# CLassD_amp_v1.net
KiCad netlist of a schematic drawn in Altium Designer
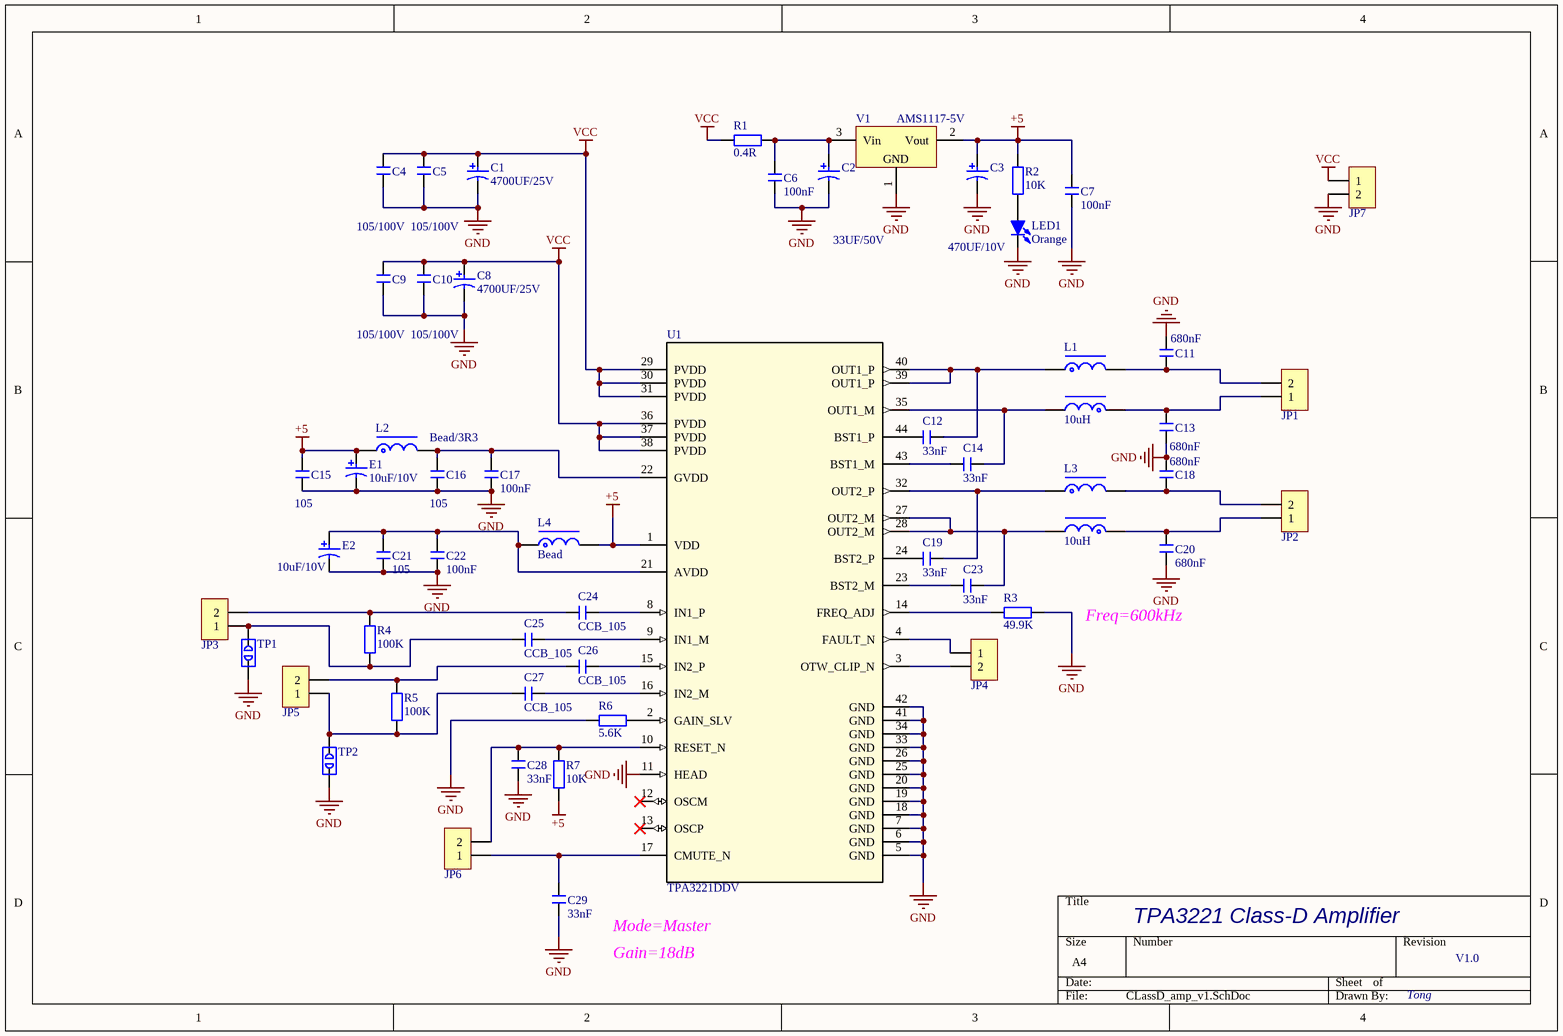
[diagram p0: CLassD_amp_v1.SchDoc]

(export (version "E")
  (design (tool "Eeschema 10.0.6"))
  (components
    (comp (ref "C1")
      (value "4700UF/25V")
      (footprint "CAP 7.5*16*31.5")
      (description "铝电解电容-直插")
      (libsource (lib "A") (part "Cap-AE-RAD"))
    )
    (comp (ref "C2")
      (value "33UF/50V")
      (footprint "CAP 2.5*6.3*11.2")
      (description "铝电解电容-直插")
      (libsource (lib "A") (part "Cap-AE-RAD"))
    )
    (comp (ref "C3")
      (value "470UF/10V")
      (footprint "CAP 2.5*6.3*11.2")
      (description "铝电解电容-直插")
      (libsource (lib "A") (part "Cap-AE-RAD"))
    )
    (comp (ref "C4")
      (value "105/100V")
      (footprint "C 1206_little")
      (description "瓷片电容-贴片")
      (libsource (lib "A") (part "Cap-CER-SMD"))
    )
    (comp (ref "C5")
      (value "105/100V")
      (footprint "C 1206_little")
      (description "瓷片电容-贴片")
      (libsource (lib "A") (part "Cap-CER-SMD"))
    )
    (comp (ref "C6")
      (value "100nF")
      (footprint "C 0603")
      (description "瓷片电容-贴片")
      (libsource (lib "A") (part "Cap-CER-SMD"))
    )
    (comp (ref "C7")
      (value "100nF")
      (footprint "C 0603")
      (description "瓷片电容-贴片")
      (libsource (lib "A") (part "Cap-CER-SMD"))
    )
    (comp (ref "C8")
      (value "4700UF/25V")
      (footprint "CAP 7.5*16*31.5")
      (description "铝电解电容-直插")
      (libsource (lib "A") (part "Cap-AE-RAD"))
    )
    (comp (ref "C9")
      (value "105/100V")
      (footprint "C 1206_little")
      (description "瓷片电容-贴片")
      (libsource (lib "A") (part "Cap-CER-SMD"))
    )
    (comp (ref "C10")
      (value "105/100V")
      (footprint "C 1206_little")
      (description "瓷片电容-贴片")
      (libsource (lib "A") (part "Cap-CER-SMD"))
    )
    (comp (ref "C11")
      (value "680nF")
      (footprint "Xcap2")
      (description "瓷片电容-贴片")
      (libsource (lib "A") (part "Cap-CER-SMD"))
    )
    (comp (ref "C12")
      (value "33nF")
      (footprint "C 0603")
      (description "瓷片电容-贴片")
      (libsource (lib "A") (part "Cap-CER-SMD"))
    )
    (comp (ref "C13")
      (value "680nF")
      (footprint "Xcap2")
      (description "瓷片电容-贴片")
      (libsource (lib "A") (part "Cap-CER-SMD"))
    )
    (comp (ref "C14")
      (value "33nF")
      (footprint "C 0603")
      (description "瓷片电容-贴片")
      (libsource (lib "A") (part "Cap-CER-SMD"))
    )
    (comp (ref "C15")
      (value "105")
      (footprint "C 0603")
      (description "瓷片电容-贴片")
      (libsource (lib "A") (part "Cap-CER-SMD"))
    )
    (comp (ref "C16")
      (value "105")
      (footprint "C 0603")
      (description "瓷片电容-贴片")
      (libsource (lib "A") (part "Cap-CER-SMD"))
    )
    (comp (ref "C17")
      (value "100nF")
      (footprint "C 0603")
      (description "瓷片电容-贴片")
      (libsource (lib "A") (part "Cap-CER-SMD"))
    )
    (comp (ref "C18")
      (value "680nF")
      (footprint "Xcap2")
      (description "瓷片电容-贴片")
      (libsource (lib "A") (part "Cap-CER-SMD"))
    )
    (comp (ref "C19")
      (value "33nF")
      (footprint "C 0603")
      (description "瓷片电容-贴片")
      (libsource (lib "A") (part "Cap-CER-SMD"))
    )
    (comp (ref "C20")
      (value "680nF")
      (footprint "Xcap2")
      (description "瓷片电容-贴片")
      (libsource (lib "A") (part "Cap-CER-SMD"))
    )
    (comp (ref "C21")
      (value "105")
      (footprint "C 0603")
      (description "瓷片电容-贴片")
      (libsource (lib "A") (part "Cap-CER-SMD"))
    )
    (comp (ref "C22")
      (value "100nF")
      (footprint "C 0603")
      (description "瓷片电容-贴片")
      (libsource (lib "A") (part "Cap-CER-SMD"))
    )
    (comp (ref "C23")
      (value "33nF")
      (footprint "C 0603")
      (description "瓷片电容-贴片")
      (libsource (lib "A") (part "Cap-CER-SMD"))
    )
    (comp (ref "C24")
      (value "CCB_105")
      (footprint "CCB_Cap_7.5mm")
      (description "瓷片电容-贴片")
      (libsource (lib "A") (part "Cap-CER-SMD"))
    )
    (comp (ref "C25")
      (value "CCB_105")
      (footprint "CCB_Cap_7.5mm")
      (description "瓷片电容-贴片")
      (libsource (lib "A") (part "Cap-CER-SMD"))
    )
    (comp (ref "C26")
      (value "CCB_105")
      (footprint "CCB_Cap_7.5mm")
      (description "瓷片电容-贴片")
      (libsource (lib "A") (part "Cap-CER-SMD"))
    )
    (comp (ref "C27")
      (value "CCB_105")
      (footprint "CCB_Cap_7.5mm")
      (description "瓷片电容-贴片")
      (libsource (lib "A") (part "Cap-CER-SMD"))
    )
    (comp (ref "C28")
      (value "33nF")
      (footprint "C 0603")
      (description "瓷片电容-贴片")
      (libsource (lib "A") (part "Cap-CER-SMD"))
    )
    (comp (ref "C29")
      (value "33nF")
      (footprint "C 0603")
      (description "瓷片电容-贴片")
      (libsource (lib "A") (part "Cap-CER-SMD"))
    )
    (comp (ref "E1")
      (value "10uF/10V")
      (footprint "CD B(3528)")
      (description "钽电解电容-贴片")
      (libsource (lib "A") (part "Cap-TAN-SMD"))
    )
    (comp (ref "E2")
      (value "10uF/10V")
      (footprint "CD B(3528)")
      (description "钽电解电容-贴片")
      (libsource (lib "A") (part "Cap-TAN-SMD"))
    )
    (comp (ref "JP1")
      (value "HDR-1X2")
      (footprint "KF128-3.81-2P")
      (description "2P接插件")
      (fields (field (name "版权归属") "源创客"))
      (libsource (lib "A") (part "Header 2"))
    )
    (comp (ref "JP2")
      (value "HDR-1X2")
      (footprint "KF128-3.81-2P")
      (description "2P接插件")
      (fields (field (name "版权归属") "源创客"))
      (libsource (lib "A") (part "Header 2"))
    )
    (comp (ref "JP3")
      (value "HDR-1X2")
      (footprint "HDR-1X2")
      (description "2P接插件")
      (fields (field (name "版权归属") "源创客"))
      (libsource (lib "") (part "Header 2_2"))
    )
    (comp (ref "JP4")
      (value "HDR-1X2")
      (footprint "HDR-1X2")
      (description "2P接插件")
      (fields (field (name "版权归属") "源创客"))
      (libsource (lib "") (part "Header 2_1"))
    )
    (comp (ref "JP5")
      (value "HDR-1X2")
      (footprint "HDR-1X2")
      (description "2P接插件")
      (fields (field (name "版权归属") "源创客"))
      (libsource (lib "") (part "Header 2_2"))
    )
    (comp (ref "JP6")
      (value "HDR-1X2")
      (footprint "HDR-1X2")
      (description "2P接插件")
      (fields (field (name "版权归属") "源创客"))
      (libsource (lib "") (part "Header 2_2"))
    )
    (comp (ref "JP7")
      (value "HDR-1X2")
      (footprint "KF128-3.81-2P")
      (description "2P接插件")
      (fields (field (name "版权归属") "源创客"))
      (libsource (lib "") (part "Header 2_1"))
    )
    (comp (ref "L1") (value "10uH") (footprint "L") (libsource (lib "A") (part "L")))
    (comp (ref "L2")
      (value "Bead/3R3")
      (footprint "L 0805")
      (description "贴片电感-小功率")
      (libsource (lib "A") (part "Ind-Beads-SMD"))
    )
    (comp (ref "L3") (value "10uH") (footprint "L") (libsource (lib "A") (part "L")))
    (comp (ref "L4")
      (value "Bead")
      (footprint "L 0805")
      (description "贴片电感-小功率")
      (libsource (lib "A") (part "Ind-Beads-SMD"))
    )
    (comp (ref "LED1")
      (value "Orange")
      (footprint "LED 0603R")
      (description "LED")
      (fields (field (name "版权归属") "源创客"))
      (libsource (lib "A") (part "LED-SMD"))
    )
    (comp (ref "R1")
      (value "0.4R")
      (footprint "Res-SMD-1206")
      (description "固定电阻器-贴片")
      (libsource (lib "A") (part "Res-Fixed-SMD"))
    )
    (comp (ref "R2")
      (value "10K")
      (footprint "Res-SMD-0603")
      (description "固定电阻器-贴片")
      (libsource (lib "A") (part "Res-Fixed-SMD"))
    )
    (comp (ref "R3")
      (value "49.9K")
      (footprint "Res-SMD-0603")
      (description "固定电阻器-贴片")
      (libsource (lib "A") (part "Res-Fixed-SMD"))
    )
    (comp (ref "R4")
      (value "100K")
      (footprint "Res-SMD-0603")
      (description "固定电阻器-贴片")
      (libsource (lib "A") (part "Res-Fixed-SMD"))
    )
    (comp (ref "R5")
      (value "100K")
      (footprint "Res-SMD-0603")
      (description "固定电阻器-贴片")
      (libsource (lib "A") (part "Res-Fixed-SMD"))
    )
    (comp (ref "R6")
      (value "5.6K")
      (footprint "Res-SMD-0603")
      (description "固定电阻器-贴片")
      (libsource (lib "A") (part "Res-Fixed-SMD"))
    )
    (comp (ref "R7")
      (value "10K")
      (footprint "Res-SMD-0603")
      (description "固定电阻器-贴片")
      (libsource (lib "A") (part "Res-Fixed-SMD"))
    )
    (comp (ref "TP1")
      (value "~")
      (footprint "DEBUG PAD2")
      (description "调试断点焊盘")
      (fields (field (name "版权归属") "源创客"))
      (libsource (lib "A") (part "DEBUG"))
    )
    (comp (ref "TP2")
      (value "~")
      (footprint "DEBUG PAD2")
      (description "调试断点焊盘")
      (fields (field (name "版权归属") "源创客"))
      (libsource (lib "A") (part "DEBUG"))
    )
    (comp (ref "U1")
      (value "TPA3221DDV")
      (footprint "DDV0044D_N")
      (description "No Description Available")
      (fields
        (field (name "MANUFACTURER") "Texas Instruments")
        (field (name "PARTNUMBER") "TPA3221DDVR")
        (field (name "COPYRIGHT") "Copyright (C) 2018 Accelerated Designs. All rights reserved")
      )
      (libsource (lib "A") (part "TPA3221DDV"))
    )
    (comp (ref "V1")
      (value "AMS1117-5V")
      (footprint "SOT223_L")
      (description "三端稳压芯片")
      (fields (field (name "版权归属") "源创客"))
      (libsource (lib "A") (part "AMS1117"))
    )
  )
  (nets
    (net (code "1") (name "+5") (class "Default")
      (node (ref "C15") (pin "2") (pinfunction "2_2") (pintype "passive"))
      (node (ref "C3") (pin "A") (pinfunction "A_A") (pintype "passive"))
      (node (ref "C7") (pin "2") (pinfunction "2_2") (pintype "passive"))
      (node (ref "E1") (pin "A") (pinfunction "A_A") (pintype "passive"))
      (node (ref "L2") (pin "1") (pinfunction "1_1") (pintype "passive"))
      (node (ref "L4") (pin "2") (pinfunction "2_2") (pintype "passive"))
      (node (ref "R2") (pin "2") (pinfunction "2_2") (pintype "passive"))
      (node (ref "R7") (pin "1") (pinfunction "1_1") (pintype "passive"))
      (node (ref "U1") (pin "1") (pinfunction "VDD_1") (pintype "power_in"))
      (node (ref "V1") (pin "2") (pinfunction "Vout_2") (pintype "passive"))
    )
    (net (code "2") (name "GND") (class "Default")
      (node (ref "C1") (pin "K") (pinfunction "K_K") (pintype "passive"))
      (node (ref "C10") (pin "2") (pinfunction "2_2") (pintype "passive"))
      (node (ref "C11") (pin "2") (pinfunction "2_2") (pintype "passive"))
      (node (ref "C13") (pin "2") (pinfunction "2_2") (pintype "passive"))
      (node (ref "C15") (pin "1") (pinfunction "1_1") (pintype "passive"))
      (node (ref "C16") (pin "1") (pinfunction "1_1") (pintype "passive"))
      (node (ref "C17") (pin "1") (pinfunction "1_1") (pintype "passive"))
      (node (ref "C18") (pin "2") (pinfunction "2_2") (pintype "passive"))
      (node (ref "C2") (pin "K") (pinfunction "K_K") (pintype "passive"))
      (node (ref "C20") (pin "2") (pinfunction "2_2") (pintype "passive"))
      (node (ref "C21") (pin "1") (pinfunction "1_1") (pintype "passive"))
      (node (ref "C22") (pin "1") (pinfunction "1_1") (pintype "passive"))
      (node (ref "C28") (pin "2") (pinfunction "2_2") (pintype "passive"))
      (node (ref "C29") (pin "2") (pinfunction "2_2") (pintype "passive"))
      (node (ref "C3") (pin "K") (pinfunction "K_K") (pintype "passive"))
      (node (ref "C4") (pin "2") (pinfunction "2_2") (pintype "passive"))
      (node (ref "C5") (pin "2") (pinfunction "2_2") (pintype "passive"))
      (node (ref "C6") (pin "1") (pinfunction "1_1") (pintype "passive"))
      (node (ref "C7") (pin "1") (pinfunction "1_1") (pintype "passive"))
      (node (ref "C8") (pin "K") (pinfunction "K_K") (pintype "passive"))
      (node (ref "C9") (pin "2") (pinfunction "2_2") (pintype "passive"))
      (node (ref "E1") (pin "K") (pinfunction "K_K") (pintype "passive"))
      (node (ref "E2") (pin "K") (pinfunction "K_K") (pintype "passive"))
      (node (ref "JP7") (pin "2") (pinfunction "2_2") (pintype "passive"))
      (node (ref "LED1") (pin "2") (pinfunction "K_2") (pintype "passive"))
      (node (ref "R3") (pin "2") (pinfunction "2_2") (pintype "passive"))
      (node (ref "R6") (pin "1") (pinfunction "1_1") (pintype "passive"))
      (node (ref "TP1") (pin "1") (pinfunction "1_1") (pintype "passive"))
      (node (ref "TP2") (pin "1") (pinfunction "1_1") (pintype "passive"))
      (node (ref "U1") (pin "11") (pinfunction "HEAD_11") (pintype "input"))
      (node (ref "U1") (pin "18") (pinfunction "GND_18") (pintype "power_in"))
      (node (ref "U1") (pin "19") (pinfunction "GND_19") (pintype "power_in"))
      (node (ref "U1") (pin "20") (pinfunction "GND_20") (pintype "power_in"))
      (node (ref "U1") (pin "25") (pinfunction "GND_25") (pintype "power_in"))
      (node (ref "U1") (pin "26") (pinfunction "GND_26") (pintype "power_in"))
      (node (ref "U1") (pin "33") (pinfunction "GND_33") (pintype "power_in"))
      (node (ref "U1") (pin "34") (pinfunction "GND_34") (pintype "power_in"))
      (node (ref "U1") (pin "41") (pinfunction "GND_41") (pintype "power_in"))
      (node (ref "U1") (pin "42") (pinfunction "GND_42") (pintype "power_in"))
      (node (ref "U1") (pin "5") (pinfunction "GND_5") (pintype "power_in"))
      (node (ref "U1") (pin "6") (pinfunction "GND_6") (pintype "power_in"))
      (node (ref "U1") (pin "7") (pinfunction "GND_7") (pintype "power_in"))
      (node (ref "V1") (pin "1") (pinfunction "GND_1") (pintype "passive"))
    )
    (net (code "3") (name "Net-(C11-Pad1)") (class "Default")
      (node (ref "C11") (pin "1") (pinfunction "1_1") (pintype "passive"))
      (node (ref "JP1") (pin "2") (pinfunction "2_2") (pintype "passive"))
      (node (ref "L1") (pin "2") (pinfunction "2_2") (pintype "passive"))
    )
    (net (code "4") (name "Net-(C12-Pad2)") (class "Default")
      (node (ref "C12") (pin "2") (pinfunction "2_2") (pintype "passive"))
      (node (ref "L1") (pin "1") (pinfunction "1_1") (pintype "passive"))
      (node (ref "U1") (pin "39") (pinfunction "OUT1_P_39") (pintype "output"))
      (node (ref "U1") (pin "40") (pinfunction "OUT1_P_40") (pintype "output"))
    )
    (net (code "5") (name "Net-(C13-Pad1)") (class "Default")
      (node (ref "C13") (pin "1") (pinfunction "1_1") (pintype "passive"))
      (node (ref "JP1") (pin "1") (pinfunction "1_1") (pintype "passive"))
      (node (ref "L1") (pin "4") (pinfunction "4_4") (pintype "passive"))
    )
    (net (code "6") (name "Net-(C18-Pad1)") (class "Default")
      (node (ref "C18") (pin "1") (pinfunction "1_1") (pintype "passive"))
      (node (ref "JP2") (pin "2") (pinfunction "2_2") (pintype "passive"))
      (node (ref "L3") (pin "2") (pinfunction "2_2") (pintype "passive"))
    )
    (net (code "7") (name "Net-(C20-Pad1)") (class "Default")
      (node (ref "C20") (pin "1") (pinfunction "1_1") (pintype "passive"))
      (node (ref "JP2") (pin "1") (pinfunction "1_1") (pintype "passive"))
      (node (ref "L3") (pin "4") (pinfunction "4_4") (pintype "passive"))
    )
    (net (code "8") (name "Net-(C23-Pad2)") (class "Default")
      (node (ref "C23") (pin "2") (pinfunction "2_2") (pintype "passive"))
      (node (ref "L3") (pin "3") (pinfunction "3_3") (pintype "passive"))
      (node (ref "U1") (pin "27") (pinfunction "OUT2_M_27") (pintype "output"))
      (node (ref "U1") (pin "28") (pinfunction "OUT2_M_28") (pintype "output"))
    )
    (net (code "9") (name "Net-(C24-Pad1)") (class "Default")
      (node (ref "C24") (pin "1") (pinfunction "1_1") (pintype "passive"))
      (node (ref "JP3") (pin "2") (pinfunction "2_2") (pintype "passive"))
      (node (ref "R4") (pin "2") (pinfunction "2_2") (pintype "passive"))
    )
    (net (code "10") (name "Net-(C25-Pad1)") (class "Default")
      (node (ref "C25") (pin "1") (pinfunction "1_1") (pintype "passive"))
      (node (ref "JP3") (pin "1") (pinfunction "1_1") (pintype "passive"))
      (node (ref "R4") (pin "1") (pinfunction "1_1") (pintype "passive"))
      (node (ref "TP1") (pin "2") (pinfunction "2_2") (pintype "passive"))
    )
    (net (code "11") (name "Net-(C26-Pad1)") (class "Default")
      (node (ref "C26") (pin "1") (pinfunction "1_1") (pintype "passive"))
      (node (ref "JP5") (pin "2") (pinfunction "2_2") (pintype "passive"))
      (node (ref "R5") (pin "2") (pinfunction "2_2") (pintype "passive"))
    )
    (net (code "12") (name "Net-(C27-Pad1)") (class "Default")
      (node (ref "C27") (pin "1") (pinfunction "1_1") (pintype "passive"))
      (node (ref "JP5") (pin "1") (pinfunction "1_1") (pintype "passive"))
      (node (ref "R5") (pin "1") (pinfunction "1_1") (pintype "passive"))
      (node (ref "TP2") (pin "2") (pinfunction "2_2") (pintype "passive"))
    )
    (net (code "13") (name "Net-(LED1-A)") (class "Default")
      (node (ref "LED1") (pin "1") (pinfunction "A_1") (pintype "passive"))
      (node (ref "R2") (pin "1") (pinfunction "1_1") (pintype "passive"))
    )
    (net (code "14") (name "Net-(U1-AVDD)") (class "Default")
      (node (ref "C21") (pin "2") (pinfunction "2_2") (pintype "passive"))
      (node (ref "C22") (pin "2") (pinfunction "2_2") (pintype "passive"))
      (node (ref "E2") (pin "A") (pinfunction "A_A") (pintype "passive"))
      (node (ref "L4") (pin "1") (pinfunction "1_1") (pintype "passive"))
      (node (ref "U1") (pin "21") (pinfunction "AVDD_21") (pintype "power_in"))
    )
    (net (code "15") (name "Net-(U1-BST1_M)") (class "Default")
      (node (ref "C14") (pin "1") (pinfunction "1_1") (pintype "passive"))
      (node (ref "U1") (pin "43") (pinfunction "BST1_M_43") (pintype "power_in"))
    )
    (net (code "16") (name "Net-(U1-BST1_P)") (class "Default")
      (node (ref "C12") (pin "1") (pinfunction "1_1") (pintype "passive"))
      (node (ref "U1") (pin "44") (pinfunction "BST1_P_44") (pintype "power_in"))
    )
    (net (code "17") (name "Net-(U1-BST2_M)") (class "Default")
      (node (ref "C23") (pin "1") (pinfunction "1_1") (pintype "passive"))
      (node (ref "U1") (pin "23") (pinfunction "BST2_M_23") (pintype "power_in"))
    )
    (net (code "18") (name "Net-(U1-BST2_P)") (class "Default")
      (node (ref "C19") (pin "1") (pinfunction "1_1") (pintype "passive"))
      (node (ref "U1") (pin "24") (pinfunction "BST2_P_24") (pintype "power_in"))
    )
    (net (code "19") (name "Net-(U1-CMUTE_N)") (class "Default")
      (node (ref "C29") (pin "1") (pinfunction "1_1") (pintype "passive"))
      (node (ref "JP6") (pin "1") (pinfunction "1_1") (pintype "passive"))
      (node (ref "U1") (pin "17") (pinfunction "CMUTE_N_17") (pintype "power_in"))
    )
    (net (code "20") (name "Net-(U1-FAULT_N)") (class "Default")
      (node (ref "JP4") (pin "1") (pinfunction "1_1") (pintype "passive"))
      (node (ref "U1") (pin "4") (pinfunction "FAULT_N_4") (pintype "output"))
    )
    (net (code "21") (name "Net-(U1-FREQ_ADJ)") (class "Default")
      (node (ref "R3") (pin "1") (pinfunction "1_1") (pintype "passive"))
      (node (ref "U1") (pin "14") (pinfunction "FREQ_ADJ_14") (pintype "output"))
    )
    (net (code "22") (name "Net-(U1-GAIN_SLV)") (class "Default")
      (node (ref "R6") (pin "2") (pinfunction "2_2") (pintype "passive"))
      (node (ref "U1") (pin "2") (pinfunction "GAIN_SLV_2") (pintype "input"))
    )
    (net (code "23") (name "Net-(U1-GVDD)") (class "Default")
      (node (ref "C16") (pin "2") (pinfunction "2_2") (pintype "passive"))
      (node (ref "C17") (pin "2") (pinfunction "2_2") (pintype "passive"))
      (node (ref "L2") (pin "2") (pinfunction "2_2") (pintype "passive"))
      (node (ref "U1") (pin "22") (pinfunction "GVDD_22") (pintype "power_in"))
    )
    (net (code "24") (name "Net-(U1-IN1_M)") (class "Default")
      (node (ref "C25") (pin "2") (pinfunction "2_2") (pintype "passive"))
      (node (ref "U1") (pin "9") (pinfunction "IN1_M_9") (pintype "input"))
    )
    (net (code "25") (name "Net-(U1-IN1_P)") (class "Default")
      (node (ref "C24") (pin "2") (pinfunction "2_2") (pintype "passive"))
      (node (ref "U1") (pin "8") (pinfunction "IN1_P_8") (pintype "input"))
    )
    (net (code "26") (name "Net-(U1-IN2_M)") (class "Default")
      (node (ref "C27") (pin "2") (pinfunction "2_2") (pintype "passive"))
      (node (ref "U1") (pin "16") (pinfunction "IN2_M_16") (pintype "input"))
    )
    (net (code "27") (name "Net-(U1-IN2_P)") (class "Default")
      (node (ref "C26") (pin "2") (pinfunction "2_2") (pintype "passive"))
      (node (ref "U1") (pin "15") (pinfunction "IN2_P_15") (pintype "input"))
    )
    (net (code "28") (name "Net-(U1-OTW_CLIP_N)") (class "Default")
      (node (ref "JP4") (pin "2") (pinfunction "2_2") (pintype "passive"))
      (node (ref "U1") (pin "3") (pinfunction "OTW_CLIP_N_3") (pintype "output"))
    )
    (net (code "29") (name "Net-(U1-OUT1_M)") (class "Default")
      (node (ref "C14") (pin "2") (pinfunction "2_2") (pintype "passive"))
      (node (ref "L1") (pin "3") (pinfunction "3_3") (pintype "passive"))
      (node (ref "U1") (pin "35") (pinfunction "OUT1_M_35") (pintype "output"))
    )
    (net (code "30") (name "Net-(U1-OUT2_P)") (class "Default")
      (node (ref "C19") (pin "2") (pinfunction "2_2") (pintype "passive"))
      (node (ref "L3") (pin "1") (pinfunction "1_1") (pintype "passive"))
      (node (ref "U1") (pin "32") (pinfunction "OUT2_P_32") (pintype "output"))
    )
    (net (code "31") (name "Net-(U1-RESET_N)") (class "Default")
      (node (ref "C28") (pin "1") (pinfunction "1_1") (pintype "passive"))
      (node (ref "JP6") (pin "2") (pinfunction "2_2") (pintype "passive"))
      (node (ref "R7") (pin "2") (pinfunction "2_2") (pintype "passive"))
      (node (ref "U1") (pin "10") (pinfunction "RESET_N_10") (pintype "input"))
    )
    (net (code "32") (name "Net-(V1-Vin)") (class "Default")
      (node (ref "C2") (pin "A") (pinfunction "A_A") (pintype "passive"))
      (node (ref "C6") (pin "2") (pinfunction "2_2") (pintype "passive"))
      (node (ref "R1") (pin "2") (pinfunction "2_2") (pintype "passive"))
      (node (ref "V1") (pin "3") (pinfunction "Vin_3") (pintype "passive"))
    )
    (net (code "33") (name "VCC") (class "Default")
      (node (ref "C1") (pin "A") (pinfunction "A_A") (pintype "passive"))
      (node (ref "C10") (pin "1") (pinfunction "1_1") (pintype "passive"))
      (node (ref "C4") (pin "1") (pinfunction "1_1") (pintype "passive"))
      (node (ref "C5") (pin "1") (pinfunction "1_1") (pintype "passive"))
      (node (ref "C8") (pin "A") (pinfunction "A_A") (pintype "passive"))
      (node (ref "C9") (pin "1") (pinfunction "1_1") (pintype "passive"))
      (node (ref "JP7") (pin "1") (pinfunction "1_1") (pintype "passive"))
      (node (ref "R1") (pin "1") (pinfunction "1_1") (pintype "passive"))
      (node (ref "U1") (pin "29") (pinfunction "PVDD_29") (pintype "power_in"))
      (node (ref "U1") (pin "30") (pinfunction "PVDD_30") (pintype "power_in"))
      (node (ref "U1") (pin "31") (pinfunction "PVDD_31") (pintype "power_in"))
      (node (ref "U1") (pin "36") (pinfunction "PVDD_36") (pintype "power_in"))
      (node (ref "U1") (pin "37") (pinfunction "PVDD_37") (pintype "power_in"))
      (node (ref "U1") (pin "38") (pinfunction "PVDD_38") (pintype "power_in"))
    )
    (net (code "34") (name "unconnected-(U1-OSCM-Pad12)") (class "Default")
      (node (ref "U1") (pin "12") (pinfunction "OSCM_12") (pintype "bidirectional+no_connect"))
    )
    (net (code "35") (name "unconnected-(U1-OSCP-Pad13)") (class "Default")
      (node (ref "U1") (pin "13") (pinfunction "OSCP_13") (pintype "bidirectional+no_connect"))
    )
  )
)
